# Sheet.net
KiCad netlist of a schematic drawn in Altium Designer
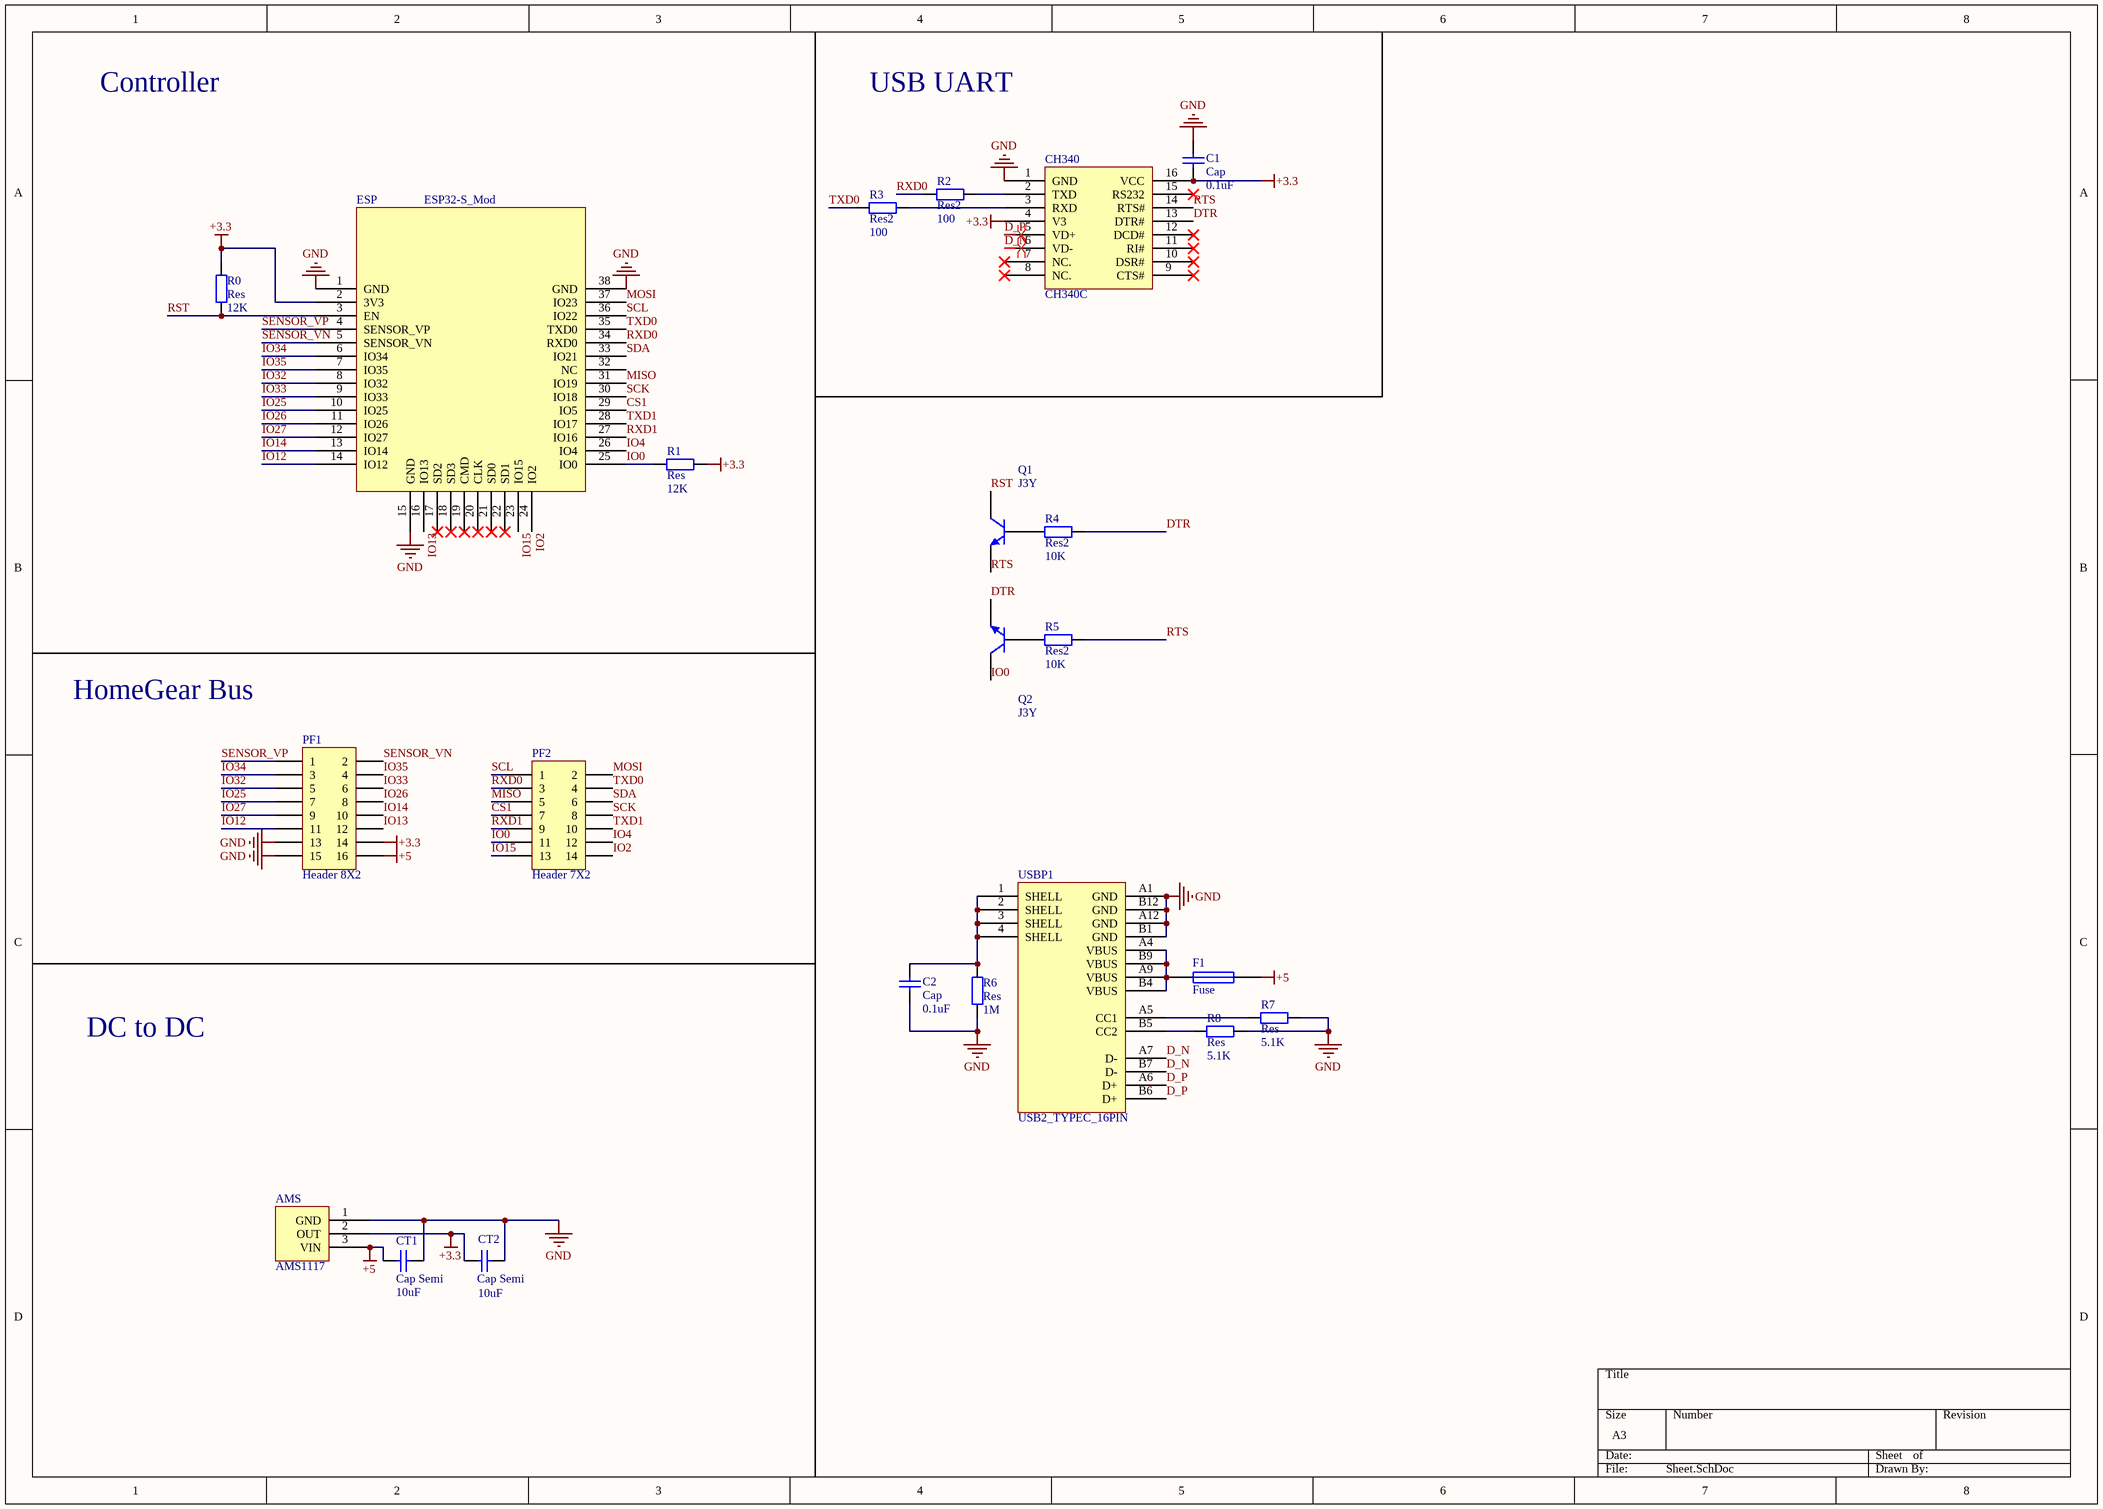
[diagram p0: Sheet.SchDoc]

(export (version "E")
  (design (tool "Eeschema 10.0.6"))
  (components
    (comp (ref "AMS") (value "AMS1117") (footprint "SOT-223-2") (libsource (lib "Schlib2") (part "AMS1117")))
    (comp (ref "C1")
      (value "Cap")
      (footprint "MY0603")
      (description "Capacitor")
      (fields (field (name "ALTIUM_VALUE") "0.1uF") (field (name "PUBLISHER") "Altium Limited"))
      (libsource (lib "Miscellaneous Devices") (part "Cap"))
    )
    (comp (ref "C2")
      (value "Cap")
      (footprint "MY0603")
      (description "Capacitor")
      (fields (field (name "ALTIUM_VALUE") "0.1uF") (field (name "PUBLISHER") "Altium Limited"))
      (libsource (lib "Miscellaneous Devices") (part "Cap"))
    )
    (comp (ref "CH340") (value "CH340C") (footprint "SOP16") (libsource (lib "我的元件库") (part "CH340C")))
    (comp (ref "CT1")
      (value "Cap Semi")
      (footprint "My1206")
      (description "Capacitor (Semiconductor SIM Model)")
      (fields (field (name "ALTIUM_VALUE") "10uF") (field (name "PUBLISHER") "Altium Limited"))
      (libsource (lib "Miscellaneous Devices") (part "Cap Semi"))
    )
    (comp (ref "CT2")
      (value "Cap Semi")
      (footprint "My1206")
      (description "Capacitor (Semiconductor SIM Model)")
      (fields (field (name "ALTIUM_VALUE") "10uF") (field (name "PUBLISHER") "Altium Limited"))
      (libsource (lib "Miscellaneous Devices") (part "Cap Semi"))
    )
    (comp (ref "ESP")
      (value "ESP32-S_Mod")
      (footprint "ESP32-S_Mod")
      (libsource (lib "我的元件库") (part "ESP32-S_Mod"))
    )
    (comp (ref "F1")
      (value "Fuse")
      (footprint "My1206")
      (fields (field (name "PUBLISHER") "Altium Limited"))
      (libsource (lib "Miscellaneous Devices") (part "Fuse 1"))
    )
    (comp (ref "PF1")
      (value "Header 8X2")
      (footprint "SMD_FEM_HDR8x2_2.0MM")
      (description "Header, 8-Pin, Dual row")
      (fields (field (name "PUBLISHER") "Altium Limited"))
      (libsource (lib "Miscellaneous Connectors") (part "Header 8X2"))
    )
    (comp (ref "PF2")
      (value "Header 7X2")
      (footprint "SMD_FEM_HDR7x2_2.0MM")
      (description "Header, 7-Pin, Dual row")
      (fields (field (name "PUBLISHER") "Altium Limited"))
      (libsource (lib "Miscellaneous Connectors") (part "Header 7X2"))
    )
    (comp (ref "Q1")
      (value "J3Y")
      (footprint "SOT-23B_N")
      (description "NPN Bipolar Transistor")
      (fields (field (name "PUBLISHER") "Altium Limited"))
      (libsource (lib "Miscellaneous Devices") (part "QNPN"))
    )
    (comp (ref "Q2")
      (value "J3Y")
      (footprint "SOT-23B_N")
      (description "NPN Bipolar Transistor")
      (fields (field (name "PUBLISHER") "Altium Limited"))
      (libsource (lib "Miscellaneous Devices") (part "QNPN"))
    )
    (comp (ref "R0")
      (value "Res")
      (footprint "MY0603")
      (description "Resistor")
      (fields (field (name "ALTIUM_VALUE") "12K") (field (name "PUBLISHER") "Altium Limited"))
      (libsource (lib "") (part "Res2_1"))
    )
    (comp (ref "R1")
      (value "Res")
      (footprint "MY0603")
      (description "Resistor")
      (fields (field (name "ALTIUM_VALUE") "12K") (field (name "PUBLISHER") "Altium Limited"))
      (libsource (lib "") (part "Res2_2"))
    )
    (comp (ref "R2")
      (value "Res2")
      (footprint "MY0603")
      (description "Resistor")
      (fields (field (name "ALTIUM_VALUE") "100") (field (name "PUBLISHER") "Altium Limited"))
      (libsource (lib "Miscellaneous Devices") (part "Res2"))
    )
    (comp (ref "R3")
      (value "Res2")
      (footprint "MY0603")
      (description "Resistor")
      (fields (field (name "ALTIUM_VALUE") "100") (field (name "PUBLISHER") "Altium Limited"))
      (libsource (lib "Miscellaneous Devices") (part "Res2"))
    )
    (comp (ref "R4")
      (value "Res2")
      (footprint "MY0603")
      (description "Resistor")
      (fields (field (name "ALTIUM_VALUE") "10K") (field (name "PUBLISHER") "Altium Limited"))
      (libsource (lib "Miscellaneous Devices") (part "Res2"))
    )
    (comp (ref "R5")
      (value "Res2")
      (footprint "MY0603")
      (description "Resistor")
      (fields (field (name "ALTIUM_VALUE") "10K") (field (name "PUBLISHER") "Altium Limited"))
      (libsource (lib "Miscellaneous Devices") (part "Res2"))
    )
    (comp (ref "R6")
      (value "Res")
      (footprint "MY0603")
      (description "Resistor")
      (fields (field (name "ALTIUM_VALUE") "1M") (field (name "PUBLISHER") "Altium Limited"))
      (libsource (lib "") (part "Res2_1"))
    )
    (comp (ref "R7")
      (value "Res")
      (footprint "MY0603")
      (description "Resistor")
      (fields (field (name "ALTIUM_VALUE") "5.1K") (field (name "PUBLISHER") "Altium Limited"))
      (libsource (lib "") (part "Res2_2"))
    )
    (comp (ref "R8")
      (value "Res")
      (footprint "MY0603")
      (description "Resistor")
      (fields (field (name "ALTIUM_VALUE") "5.1K") (field (name "PUBLISHER") "Altium Limited"))
      (libsource (lib "") (part "Res2_2"))
    )
    (comp (ref "USBP1")
      (value "USB2_TYPEC_16PIN")
      (footprint "USB-C-SMD16P")
      (libsource (lib "我的元件库") (part "USB2_TYPEC_16PIN"))
    )
  )
  (nets
    (net (code "1") (name "+3.3") (class "Default")
      (node (ref "AMS") (pin "2") (pinfunction "OUT_2") (pintype "passive"))
      (node (ref "C1") (pin "1") (pinfunction "1_1") (pintype "passive"))
      (node (ref "CH340") (pin "16") (pinfunction "VCC_16") (pintype "passive"))
      (node (ref "CH340") (pin "4") (pinfunction "V3_4") (pintype "passive"))
      (node (ref "CT2") (pin "1") (pinfunction "1_1") (pintype "passive"))
      (node (ref "ESP") (pin "2") (pinfunction "3V3_2") (pintype "passive"))
      (node (ref "PF1") (pin "14") (pinfunction "14_14") (pintype "passive"))
      (node (ref "R0") (pin "2") (pinfunction "2_2") (pintype "passive"))
      (node (ref "R1") (pin "1") (pinfunction "1_1") (pintype "passive"))
    )
    (net (code "2") (name "+5") (class "Default")
      (node (ref "AMS") (pin "3") (pinfunction "VIN_3") (pintype "passive"))
      (node (ref "CT1") (pin "1") (pinfunction "1_1") (pintype "passive"))
      (node (ref "F1") (pin "2") (pinfunction "2_2") (pintype "passive"))
      (node (ref "PF1") (pin "16") (pinfunction "16_16") (pintype "passive"))
    )
    (net (code "3") (name "/CS1") (class "Default")
      (node (ref "ESP") (pin "29") (pinfunction "IO5_29") (pintype "passive"))
      (node (ref "PF2") (pin "7") (pinfunction "7_7") (pintype "passive"))
    )
    (net (code "4") (name "/DTR") (class "Default")
      (node (ref "CH340") (pin "13") (pinfunction "DTR#_13") (pintype "passive"))
      (node (ref "Q2") (pin "3") (pinfunction "E_3") (pintype "passive"))
      (node (ref "R4") (pin "2") (pinfunction "2_2") (pintype "passive"))
    )
    (net (code "5") (name "/D_N") (class "Default")
      (node (ref "CH340") (pin "6") (pinfunction "VD-_6") (pintype "passive"))
      (node (ref "USBP1") (pin "A7") (pinfunction "D-_A7") (pintype "passive"))
      (node (ref "USBP1") (pin "B7") (pinfunction "D-_B7") (pintype "passive"))
    )
    (net (code "6") (name "/D_P") (class "Default")
      (node (ref "CH340") (pin "5") (pinfunction "VD+_5") (pintype "passive"))
      (node (ref "USBP1") (pin "A6") (pinfunction "D+_A6") (pintype "passive"))
      (node (ref "USBP1") (pin "B6") (pinfunction "D+_B6") (pintype "passive"))
    )
    (net (code "7") (name "/IO0") (class "Default")
      (node (ref "ESP") (pin "25") (pinfunction "IO0_25") (pintype "passive"))
      (node (ref "PF2") (pin "11") (pinfunction "11_11") (pintype "passive"))
      (node (ref "Q2") (pin "1") (pinfunction "C_1") (pintype "passive"))
      (node (ref "R1") (pin "2") (pinfunction "2_2") (pintype "passive"))
    )
    (net (code "8") (name "/IO2") (class "Default")
      (node (ref "ESP") (pin "24") (pinfunction "IO2_24") (pintype "passive"))
      (node (ref "PF2") (pin "14") (pinfunction "14_14") (pintype "passive"))
    )
    (net (code "9") (name "/IO4") (class "Default")
      (node (ref "ESP") (pin "26") (pinfunction "IO4_26") (pintype "passive"))
      (node (ref "PF2") (pin "12") (pinfunction "12_12") (pintype "passive"))
    )
    (net (code "10") (name "/IO12") (class "Default")
      (node (ref "ESP") (pin "14") (pinfunction "IO12_14") (pintype "passive"))
      (node (ref "PF1") (pin "11") (pinfunction "11_11") (pintype "passive"))
    )
    (net (code "11") (name "/IO13") (class "Default")
      (node (ref "ESP") (pin "16") (pinfunction "IO13_16") (pintype "passive"))
      (node (ref "PF1") (pin "12") (pinfunction "12_12") (pintype "passive"))
    )
    (net (code "12") (name "/IO14") (class "Default")
      (node (ref "ESP") (pin "13") (pinfunction "IO14_13") (pintype "passive"))
      (node (ref "PF1") (pin "10") (pinfunction "10_10") (pintype "passive"))
    )
    (net (code "13") (name "/IO15") (class "Default")
      (node (ref "ESP") (pin "23") (pinfunction "IO15_23") (pintype "passive"))
      (node (ref "PF2") (pin "13") (pinfunction "13_13") (pintype "passive"))
    )
    (net (code "14") (name "/IO25") (class "Default")
      (node (ref "ESP") (pin "10") (pinfunction "IO25_10") (pintype "passive"))
      (node (ref "PF1") (pin "7") (pinfunction "7_7") (pintype "passive"))
    )
    (net (code "15") (name "/IO26") (class "Default")
      (node (ref "ESP") (pin "11") (pinfunction "IO26_11") (pintype "passive"))
      (node (ref "PF1") (pin "8") (pinfunction "8_8") (pintype "passive"))
    )
    (net (code "16") (name "/IO27") (class "Default")
      (node (ref "ESP") (pin "12") (pinfunction "IO27_12") (pintype "passive"))
      (node (ref "PF1") (pin "9") (pinfunction "9_9") (pintype "passive"))
    )
    (net (code "17") (name "/IO32") (class "Default")
      (node (ref "ESP") (pin "8") (pinfunction "IO32_8") (pintype "passive"))
      (node (ref "PF1") (pin "5") (pinfunction "5_5") (pintype "passive"))
    )
    (net (code "18") (name "/IO33") (class "Default")
      (node (ref "ESP") (pin "9") (pinfunction "IO33_9") (pintype "passive"))
      (node (ref "PF1") (pin "6") (pinfunction "6_6") (pintype "passive"))
    )
    (net (code "19") (name "/IO34") (class "Default")
      (node (ref "ESP") (pin "6") (pinfunction "IO34_6") (pintype "passive"))
      (node (ref "PF1") (pin "3") (pinfunction "3_3") (pintype "passive"))
    )
    (net (code "20") (name "/IO35") (class "Default")
      (node (ref "ESP") (pin "7") (pinfunction "IO35_7") (pintype "passive"))
      (node (ref "PF1") (pin "4") (pinfunction "4_4") (pintype "passive"))
    )
    (net (code "21") (name "/MISO") (class "Default")
      (node (ref "ESP") (pin "31") (pinfunction "IO19_31") (pintype "passive"))
      (node (ref "PF2") (pin "5") (pinfunction "5_5") (pintype "passive"))
    )
    (net (code "22") (name "/MOSI") (class "Default")
      (node (ref "ESP") (pin "37") (pinfunction "IO23_37") (pintype "passive"))
      (node (ref "PF2") (pin "2") (pinfunction "2_2") (pintype "passive"))
    )
    (net (code "23") (name "/RST") (class "Default")
      (node (ref "ESP") (pin "3") (pinfunction "EN_3") (pintype "passive"))
      (node (ref "Q1") (pin "1") (pinfunction "C_1") (pintype "passive"))
      (node (ref "R0") (pin "1") (pinfunction "1_1") (pintype "passive"))
    )
    (net (code "24") (name "/RTS") (class "Default")
      (node (ref "CH340") (pin "14") (pinfunction "RTS#_14") (pintype "passive"))
      (node (ref "Q1") (pin "3") (pinfunction "E_3") (pintype "passive"))
      (node (ref "R5") (pin "2") (pinfunction "2_2") (pintype "passive"))
    )
    (net (code "25") (name "/RXD0") (class "Default")
      (node (ref "ESP") (pin "34") (pinfunction "RXD0_34") (pintype "passive"))
      (node (ref "PF2") (pin "3") (pinfunction "3_3") (pintype "passive"))
      (node (ref "R2") (pin "1") (pinfunction "1_1") (pintype "passive"))
    )
    (net (code "26") (name "/RXD1") (class "Default")
      (node (ref "ESP") (pin "27") (pinfunction "IO16_27") (pintype "passive"))
      (node (ref "PF2") (pin "9") (pinfunction "9_9") (pintype "passive"))
    )
    (net (code "27") (name "/SCK") (class "Default")
      (node (ref "ESP") (pin "30") (pinfunction "IO18_30") (pintype "passive"))
      (node (ref "PF2") (pin "8") (pinfunction "8_8") (pintype "passive"))
    )
    (net (code "28") (name "/SCL") (class "Default")
      (node (ref "ESP") (pin "36") (pinfunction "IO22_36") (pintype "passive"))
      (node (ref "PF2") (pin "1") (pinfunction "1_1") (pintype "passive"))
    )
    (net (code "29") (name "/SDA") (class "Default")
      (node (ref "ESP") (pin "33") (pinfunction "IO21_33") (pintype "passive"))
      (node (ref "PF2") (pin "6") (pinfunction "6_6") (pintype "passive"))
    )
    (net (code "30") (name "/SENSOR_VN") (class "Default")
      (node (ref "ESP") (pin "5") (pinfunction "SENSOR_VN_5") (pintype "passive"))
      (node (ref "PF1") (pin "2") (pinfunction "2_2") (pintype "passive"))
    )
    (net (code "31") (name "/SENSOR_VP") (class "Default")
      (node (ref "ESP") (pin "4") (pinfunction "SENSOR_VP_4") (pintype "passive"))
      (node (ref "PF1") (pin "1") (pinfunction "1_1") (pintype "passive"))
    )
    (net (code "32") (name "/TXD0") (class "Default")
      (node (ref "ESP") (pin "35") (pinfunction "TXD0_35") (pintype "passive"))
      (node (ref "PF2") (pin "4") (pinfunction "4_4") (pintype "passive"))
      (node (ref "R3") (pin "1") (pinfunction "1_1") (pintype "passive"))
    )
    (net (code "33") (name "/TXD1") (class "Default")
      (node (ref "ESP") (pin "28") (pinfunction "IO17_28") (pintype "passive"))
      (node (ref "PF2") (pin "10") (pinfunction "10_10") (pintype "passive"))
    )
    (net (code "34") (name "GND") (class "Default")
      (node (ref "AMS") (pin "1") (pinfunction "GND_1") (pintype "passive"))
      (node (ref "C1") (pin "2") (pinfunction "2_2") (pintype "passive"))
      (node (ref "C2") (pin "1") (pinfunction "1_1") (pintype "passive"))
      (node (ref "CH340") (pin "1") (pinfunction "GND_1") (pintype "passive"))
      (node (ref "CT1") (pin "2") (pinfunction "2_2") (pintype "passive"))
      (node (ref "CT2") (pin "2") (pinfunction "2_2") (pintype "passive"))
      (node (ref "ESP") (pin "1") (pinfunction "GND_1") (pintype "passive"))
      (node (ref "ESP") (pin "15") (pinfunction "GND_15") (pintype "passive"))
      (node (ref "ESP") (pin "38") (pinfunction "GND_38") (pintype "passive"))
      (node (ref "PF1") (pin "13") (pinfunction "13_13") (pintype "passive"))
      (node (ref "PF1") (pin "15") (pinfunction "15_15") (pintype "passive"))
      (node (ref "R6") (pin "1") (pinfunction "1_1") (pintype "passive"))
      (node (ref "R7") (pin "1") (pinfunction "1_1") (pintype "passive"))
      (node (ref "R8") (pin "1") (pinfunction "1_1") (pintype "passive"))
      (node (ref "USBP1") (pin "A1") (pinfunction "GND_A1") (pintype "passive"))
      (node (ref "USBP1") (pin "A12") (pinfunction "GND_A12") (pintype "passive"))
      (node (ref "USBP1") (pin "B1") (pinfunction "GND_B1") (pintype "passive"))
      (node (ref "USBP1") (pin "B12") (pinfunction "GND_B12") (pintype "passive"))
    )
    (net (code "35") (name "Net-(C2-Pad2)") (class "Default")
      (node (ref "C2") (pin "2") (pinfunction "2_2") (pintype "passive"))
      (node (ref "R6") (pin "2") (pinfunction "2_2") (pintype "passive"))
      (node (ref "USBP1") (pin "1") (pinfunction "SHELL_1") (pintype "passive"))
      (node (ref "USBP1") (pin "2") (pinfunction "SHELL_2") (pintype "passive"))
      (node (ref "USBP1") (pin "3") (pinfunction "SHELL_3") (pintype "passive"))
      (node (ref "USBP1") (pin "4") (pinfunction "SHELL_4") (pintype "passive"))
    )
    (net (code "36") (name "Net-(CH340-RXD)") (class "Default")
      (node (ref "CH340") (pin "3") (pinfunction "RXD_3") (pintype "passive"))
      (node (ref "R3") (pin "2") (pinfunction "2_2") (pintype "passive"))
    )
    (net (code "37") (name "Net-(CH340-TXD)") (class "Default")
      (node (ref "CH340") (pin "2") (pinfunction "TXD_2") (pintype "passive"))
      (node (ref "R2") (pin "2") (pinfunction "2_2") (pintype "passive"))
    )
    (net (code "38") (name "Net-(F1-Pad1)") (class "Default")
      (node (ref "F1") (pin "1") (pinfunction "1_1") (pintype "passive"))
      (node (ref "USBP1") (pin "A4") (pinfunction "VBUS_A4") (pintype "passive"))
      (node (ref "USBP1") (pin "A9") (pinfunction "VBUS_A9") (pintype "passive"))
      (node (ref "USBP1") (pin "B4") (pinfunction "VBUS_B4") (pintype "passive"))
      (node (ref "USBP1") (pin "B9") (pinfunction "VBUS_B9") (pintype "passive"))
    )
    (net (code "39") (name "Net-(Q1-B)") (class "Default")
      (node (ref "Q1") (pin "2") (pinfunction "B_2") (pintype "passive"))
      (node (ref "R4") (pin "1") (pinfunction "1_1") (pintype "passive"))
    )
    (net (code "40") (name "Net-(Q2-B)") (class "Default")
      (node (ref "Q2") (pin "2") (pinfunction "B_2") (pintype "passive"))
      (node (ref "R5") (pin "1") (pinfunction "1_1") (pintype "passive"))
    )
    (net (code "41") (name "Net-(USBP1-CC1)") (class "Default")
      (node (ref "R7") (pin "2") (pinfunction "2_2") (pintype "passive"))
      (node (ref "USBP1") (pin "A5") (pinfunction "CC1_A5") (pintype "passive"))
    )
    (net (code "42") (name "Net-(USBP1-CC2)") (class "Default")
      (node (ref "R8") (pin "2") (pinfunction "2_2") (pintype "passive"))
      (node (ref "USBP1") (pin "B5") (pinfunction "CC2_B5") (pintype "passive"))
    )
    (net (code "43") (name "unconnected-(CH340-CTS#-Pad9)") (class "Default")
      (node (ref "CH340") (pin "9") (pinfunction "CTS#_9") (pintype "passive+no_connect"))
    )
    (net (code "44") (name "unconnected-(CH340-DCD#-Pad12)") (class "Default")
      (node (ref "CH340") (pin "12") (pinfunction "DCD#_12") (pintype "passive+no_connect"))
    )
    (net (code "45") (name "unconnected-(CH340-DSR#-Pad10)") (class "Default")
      (node (ref "CH340") (pin "10") (pinfunction "DSR#_10") (pintype "passive+no_connect"))
    )
    (net (code "46") (name "unconnected-(CH340-NC.-Pad7)") (class "Default")
      (node (ref "CH340") (pin "7") (pinfunction "NC._7") (pintype "passive+no_connect"))
    )
    (net (code "47") (name "unconnected-(CH340-NC.-Pad8)") (class "Default")
      (node (ref "CH340") (pin "8") (pinfunction "NC._8") (pintype "passive+no_connect"))
    )
    (net (code "48") (name "unconnected-(CH340-RI#-Pad11)") (class "Default")
      (node (ref "CH340") (pin "11") (pinfunction "RI#_11") (pintype "passive+no_connect"))
    )
    (net (code "49") (name "unconnected-(CH340-RS232-Pad15)") (class "Default")
      (node (ref "CH340") (pin "15") (pinfunction "RS232_15") (pintype "passive+no_connect"))
    )
    (net (code "50") (name "unconnected-(ESP-CLK-Pad20)") (class "Default")
      (node (ref "ESP") (pin "20") (pinfunction "CLK_20") (pintype "passive+no_connect"))
    )
    (net (code "51") (name "unconnected-(ESP-CMD-Pad19)") (class "Default")
      (node (ref "ESP") (pin "19") (pinfunction "CMD_19") (pintype "passive+no_connect"))
    )
    (net (code "52") (name "unconnected-(ESP-NC-Pad32)") (class "Default")
      (node (ref "ESP") (pin "32") (pinfunction "NC_32") (pintype "passive"))
    )
    (net (code "53") (name "unconnected-(ESP-SD0-Pad21)") (class "Default")
      (node (ref "ESP") (pin "21") (pinfunction "SD0_21") (pintype "passive+no_connect"))
    )
    (net (code "54") (name "unconnected-(ESP-SD1-Pad22)") (class "Default")
      (node (ref "ESP") (pin "22") (pinfunction "SD1_22") (pintype "passive+no_connect"))
    )
    (net (code "55") (name "unconnected-(ESP-SD2-Pad17)") (class "Default")
      (node (ref "ESP") (pin "17") (pinfunction "SD2_17") (pintype "passive+no_connect"))
    )
    (net (code "56") (name "unconnected-(ESP-SD3-Pad18)") (class "Default")
      (node (ref "ESP") (pin "18") (pinfunction "SD3_18") (pintype "passive+no_connect"))
    )
  )
)
